# claw.net
KiCad netlist of a schematic drawn in EAGLE
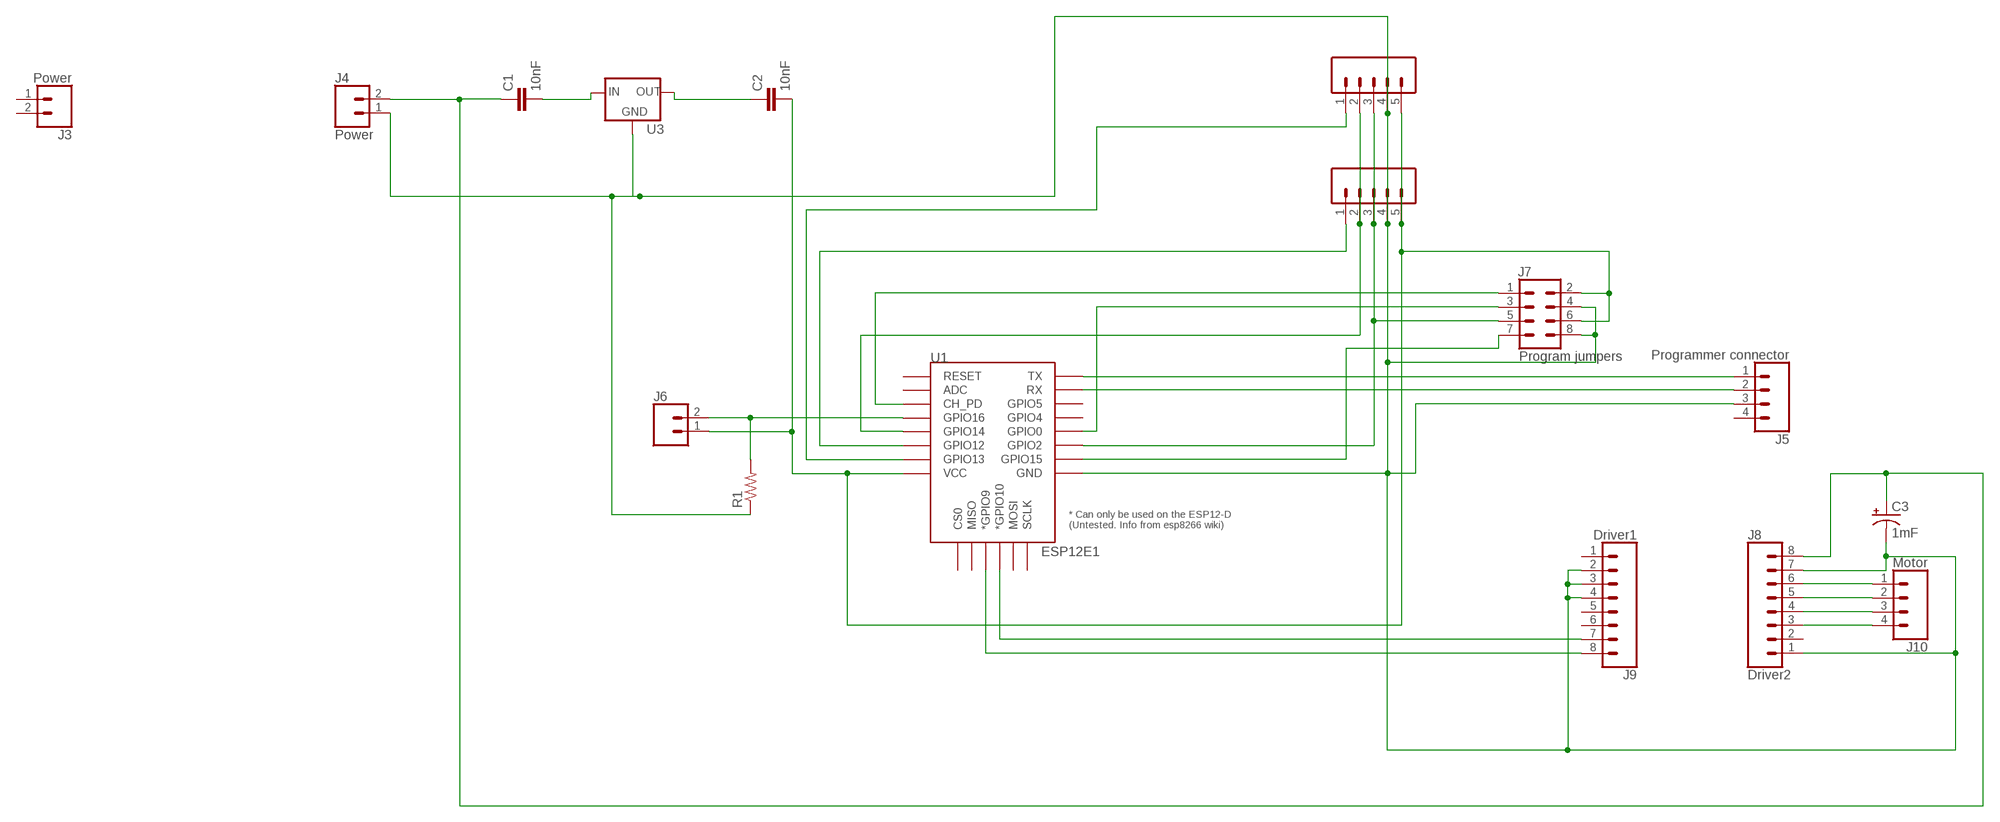
[diagram p0: schematic, sheet 1]

(export (version "E")
  (design (tool "Eeschema 10.0.6"))
  (components
    (comp (ref "C1")
      (value "10nF")
      (footprint "eagle-import:0603")
      (libsource (lib "eagle-import") (part "10NF-0603-50V-10%"))
    )
    (comp (ref "C2")
      (value "10nF")
      (footprint "eagle-import:0603")
      (libsource (lib "eagle-import") (part "10NF-0603-50V-10%"))
    )
    (comp (ref "C3")
      (value "1mF")
      (footprint "eagle-import:CPOL-RADIAL-5MM-10MM")
      (libsource (lib "eagle-import") (part "1000UF-RADIAL-5MM-25V-20%"))
    )
    (comp (ref "J1")
      (value "Sensor1")
      (footprint "eagle-import:JST-5-PTH-VERT")
      (libsource (lib "eagle-import") (part "CONN_05JST-VERT"))
    )
    (comp (ref "J2")
      (value "Sensor2")
      (footprint "eagle-import:JST-5-PTH-VERT")
      (libsource (lib "eagle-import") (part "CONN_05JST-VERT"))
    )
    (comp (ref "J3")
      (value "Power")
      (footprint "eagle-import:1X02_LOCK")
      (libsource (lib "eagle-import") (part "CONN_02LOCK"))
    )
    (comp (ref "J4")
      (value "Power")
      (footprint "eagle-import:1X02_LOCK")
      (libsource (lib "eagle-import") (part "CONN_02LOCK"))
    )
    (comp (ref "J5")
      (value "Programmer connector")
      (footprint "eagle-import:JST-4-PTH-VERT")
      (libsource (lib "eagle-import") (part "CONN_04JST-PTH-VERT"))
    )
    (comp (ref "J6")
      (value "CONN_02LOCK")
      (footprint "eagle-import:1X02_LOCK")
      (libsource (lib "eagle-import") (part "CONN_02LOCK"))
    )
    (comp (ref "J7")
      (value "Program jumpers")
      (footprint "eagle-import:2X4")
      (libsource (lib "eagle-import") (part "CONN_04X2"))
    )
    (comp (ref "J8")
      (value "Driver2")
      (footprint "eagle-import:1X08_NO_SILK")
      (libsource (lib "eagle-import") (part "CONN_08NO_SILK_FEMALE_PTH"))
    )
    (comp (ref "J9")
      (value "Driver1")
      (footprint "eagle-import:1X08_NO_SILK")
      (libsource (lib "eagle-import") (part "CONN_08NO_SILK_FEMALE_PTH"))
    )
    (comp (ref "J10")
      (value "Motor")
      (footprint "eagle-import:JST-4-PTH-VERT")
      (libsource (lib "eagle-import") (part "CONN_04JST-PTH-VERT"))
    )
    (comp (ref "R1")
      (value "R-US_M2309")
      (footprint "eagle-import:M2309")
      (libsource (lib "eagle-import") (part "R-US_M2309"))
    )
    (comp (ref "U1")
      (value "ESP12E1")
      (footprint "eagle-import:ESP12E-SMD")
      (libsource (lib "eagle-import") (part "ESP12ESMD"))
    )
    (comp (ref "U3")
      (value "V_REG_78XX-TO-220")
      (footprint "eagle-import:TO-220-ALT")
      (libsource (lib "eagle-import") (part "V_REG_78XX-TO-220"))
    )
  )
  (nets
    (net (code "1") (name "Net-(C1-Pad1)") (class "Default")
      (node (ref "C1") (pin "1") (pinfunction "1_1") (pintype "passive"))
      (node (ref "C3") (pin "+") (pinfunction "+_+") (pintype "passive"))
      (node (ref "J4") (pin "2") (pinfunction "2_2") (pintype "passive"))
      (node (ref "J8") (pin "8") (pinfunction "8_8") (pintype "passive"))
    )
    (net (code "2") (name "Net-(C1-Pad2)") (class "Default")
      (node (ref "C1") (pin "2") (pinfunction "2_2") (pintype "passive"))
      (node (ref "U3") (pin "IN") (pinfunction "IN_IN") (pintype "input"))
    )
    (net (code "3") (name "Net-(C2-Pad1)") (class "Default")
      (node (ref "C2") (pin "1") (pinfunction "1_1") (pintype "passive"))
      (node (ref "U3") (pin "OUT") (pinfunction "OUT_OUT") (pintype "passive"))
    )
    (net (code "4") (name "Net-(C2-Pad2)") (class "Default")
      (node (ref "C2") (pin "2") (pinfunction "2_2") (pintype "passive"))
      (node (ref "J1") (pin "5") (pinfunction "5_5") (pintype "passive"))
      (node (ref "J2") (pin "5") (pinfunction "5_5") (pintype "passive"))
      (node (ref "J6") (pin "1") (pinfunction "1_1") (pintype "passive"))
      (node (ref "J7") (pin "2") (pinfunction "2_2") (pintype "passive"))
      (node (ref "J7") (pin "6") (pinfunction "6_6") (pintype "passive"))
      (node (ref "U1") (pin "VCC") (pinfunction "VCC_VCC") (pintype "bidirectional"))
    )
    (net (code "5") (name "Net-(C3-Pad-)") (class "Default")
      (node (ref "C3") (pin "-") (pinfunction "-_-") (pintype "passive"))
      (node (ref "J1") (pin "4") (pinfunction "4_4") (pintype "passive"))
      (node (ref "J2") (pin "4") (pinfunction "4_4") (pintype "passive"))
      (node (ref "J4") (pin "1") (pinfunction "1_1") (pintype "passive"))
      (node (ref "J5") (pin "3") (pinfunction "3_3") (pintype "passive"))
      (node (ref "J7") (pin "4") (pinfunction "4_4") (pintype "passive"))
      (node (ref "J7") (pin "8") (pinfunction "8_8") (pintype "passive"))
      (node (ref "J8") (pin "1") (pinfunction "1_1") (pintype "passive"))
      (node (ref "J8") (pin "7") (pinfunction "7_7") (pintype "passive"))
      (node (ref "J9") (pin "2") (pinfunction "2_2") (pintype "passive"))
      (node (ref "J9") (pin "3") (pinfunction "3_3") (pintype "passive"))
      (node (ref "J9") (pin "4") (pinfunction "4_4") (pintype "passive"))
      (node (ref "R1") (pin "1") (pinfunction "1_1") (pintype "passive"))
      (node (ref "U1") (pin "GND") (pinfunction "GND_GND") (pintype "bidirectional"))
      (node (ref "U3") (pin "GND") (pinfunction "GND_GND") (pintype "input"))
    )
    (net (code "6") (name "Net-(J1-Pad1)") (class "Default")
      (node (ref "J1") (pin "1") (pinfunction "1_1") (pintype "passive"))
      (node (ref "U1") (pin "GPIO13") (pinfunction "GPIO13_GPIO13") (pintype "bidirectional"))
    )
    (net (code "7") (name "Net-(J1-Pad2)") (class "Default")
      (node (ref "J1") (pin "2") (pinfunction "2_2") (pintype "passive"))
      (node (ref "J2") (pin "2") (pinfunction "2_2") (pintype "passive"))
      (node (ref "U1") (pin "GPIO14") (pinfunction "GPIO14_GPIO14") (pintype "bidirectional"))
    )
    (net (code "8") (name "Net-(J1-Pad3)") (class "Default")
      (node (ref "J1") (pin "3") (pinfunction "3_3") (pintype "passive"))
      (node (ref "J2") (pin "3") (pinfunction "3_3") (pintype "passive"))
      (node (ref "J7") (pin "5") (pinfunction "5_5") (pintype "passive"))
      (node (ref "U1") (pin "GPIO2") (pinfunction "GPIO2_GPIO2") (pintype "bidirectional"))
    )
    (net (code "9") (name "Net-(J2-Pad1)") (class "Default")
      (node (ref "J2") (pin "1") (pinfunction "1_1") (pintype "passive"))
      (node (ref "U1") (pin "GPIO12") (pinfunction "GPIO12_GPIO12") (pintype "bidirectional"))
    )
    (net (code "10") (name "Net-(J6-Pad2)") (class "Default")
      (node (ref "J6") (pin "2") (pinfunction "2_2") (pintype "passive"))
      (node (ref "R1") (pin "2") (pinfunction "2_2") (pintype "passive"))
      (node (ref "U1") (pin "GPIO16") (pinfunction "GPIO16_GPIO16") (pintype "bidirectional"))
    )
    (net (code "11") (name "Net-(J7-Pad1)") (class "Default")
      (node (ref "J7") (pin "1") (pinfunction "1_1") (pintype "passive"))
      (node (ref "U1") (pin "CH_PD") (pinfunction "CH_PD_CH_PD") (pintype "bidirectional"))
    )
    (net (code "12") (name "Net-(J7-Pad3)") (class "Default")
      (node (ref "J7") (pin "3") (pinfunction "3_3") (pintype "passive"))
      (node (ref "U1") (pin "GPIO0") (pinfunction "GPIO0_GPIO0") (pintype "bidirectional"))
    )
    (net (code "13") (name "Net-(J7-Pad7)") (class "Default")
      (node (ref "J7") (pin "7") (pinfunction "7_7") (pintype "passive"))
      (node (ref "U1") (pin "GPIO15") (pinfunction "GPIO15_GPIO15") (pintype "bidirectional"))
    )
    (net (code "14") (name "Net-(J10-Pad1)") (class "Default")
      (node (ref "J10") (pin "1") (pinfunction "1_1") (pintype "passive"))
      (node (ref "J8") (pin "6") (pinfunction "6_6") (pintype "passive"))
    )
    (net (code "15") (name "Net-(J10-Pad2)") (class "Default")
      (node (ref "J10") (pin "2") (pinfunction "2_2") (pintype "passive"))
      (node (ref "J8") (pin "5") (pinfunction "5_5") (pintype "passive"))
    )
    (net (code "16") (name "Net-(J10-Pad3)") (class "Default")
      (node (ref "J10") (pin "3") (pinfunction "3_3") (pintype "passive"))
      (node (ref "J8") (pin "4") (pinfunction "4_4") (pintype "passive"))
    )
    (net (code "17") (name "Net-(J10-Pad4)") (class "Default")
      (node (ref "J10") (pin "4") (pinfunction "4_4") (pintype "passive"))
      (node (ref "J8") (pin "3") (pinfunction "3_3") (pintype "passive"))
    )
    (net (code "18") (name "Net-(U1-*GPIO9)") (class "Default")
      (node (ref "J9") (pin "8") (pinfunction "8_8") (pintype "passive"))
      (node (ref "U1") (pin "GPIO9") (pinfunction "*GPIO9_GPIO9") (pintype "bidirectional"))
    )
    (net (code "19") (name "Net-(U1-*GPIO10)") (class "Default")
      (node (ref "J9") (pin "7") (pinfunction "7_7") (pintype "passive"))
      (node (ref "U1") (pin "GPIO10") (pinfunction "*GPIO10_GPIO10") (pintype "bidirectional"))
    )
    (net (code "20") (name "Net-(U1-RX)") (class "Default")
      (node (ref "J5") (pin "2") (pinfunction "2_2") (pintype "passive"))
      (node (ref "U1") (pin "RXD0") (pinfunction "RX_RXD0") (pintype "bidirectional"))
    )
    (net (code "21") (name "Net-(U1-TX)") (class "Default")
      (node (ref "J5") (pin "1") (pinfunction "1_1") (pintype "passive"))
      (node (ref "U1") (pin "TXD0") (pinfunction "TX_TXD0") (pintype "bidirectional"))
    )
    (net (code "22") (name "unconnected-(J3-Pad1)") (class "Default")
      (node (ref "J3") (pin "1") (pinfunction "1_1") (pintype "passive"))
    )
    (net (code "23") (name "unconnected-(J3-Pad2)") (class "Default")
      (node (ref "J3") (pin "2") (pinfunction "2_2") (pintype "passive"))
    )
    (net (code "24") (name "unconnected-(J5-Pad4)") (class "Default")
      (node (ref "J5") (pin "4") (pinfunction "4_4") (pintype "passive"))
    )
    (net (code "25") (name "unconnected-(J8-Pad2)") (class "Default")
      (node (ref "J8") (pin "2") (pinfunction "2_2") (pintype "passive"))
    )
    (net (code "26") (name "unconnected-(J9-Pad1)") (class "Default")
      (node (ref "J9") (pin "1") (pinfunction "1_1") (pintype "passive"))
    )
    (net (code "27") (name "unconnected-(J9-Pad5)") (class "Default")
      (node (ref "J9") (pin "5") (pinfunction "5_5") (pintype "passive"))
    )
    (net (code "28") (name "unconnected-(J9-Pad6)") (class "Default")
      (node (ref "J9") (pin "6") (pinfunction "6_6") (pintype "passive"))
    )
    (net (code "29") (name "unconnected-(U1-PadADC)") (class "Default")
      (node (ref "U1") (pin "ADC") (pinfunction "ADC_ADC") (pintype "bidirectional"))
    )
    (net (code "30") (name "unconnected-(U1-PadCS0)") (class "Default")
      (node (ref "U1") (pin "CS0") (pinfunction "CS0_CS0") (pintype "bidirectional"))
    )
    (net (code "31") (name "unconnected-(U1-PadGPIO4)") (class "Default")
      (node (ref "U1") (pin "GPIO4") (pinfunction "GPIO4_GPIO4") (pintype "bidirectional"))
    )
    (net (code "32") (name "unconnected-(U1-PadGPIO5)") (class "Default")
      (node (ref "U1") (pin "GPIO5") (pinfunction "GPIO5_GPIO5") (pintype "bidirectional"))
    )
    (net (code "33") (name "unconnected-(U1-PadMISO)") (class "Default")
      (node (ref "U1") (pin "MISO") (pinfunction "MISO_MISO") (pintype "bidirectional"))
    )
    (net (code "34") (name "unconnected-(U1-PadMOSI)") (class "Default")
      (node (ref "U1") (pin "MOSI") (pinfunction "MOSI_MOSI") (pintype "bidirectional"))
    )
    (net (code "35") (name "unconnected-(U1-PadRESET)") (class "Default")
      (node (ref "U1") (pin "RESET") (pinfunction "RESET_RESET") (pintype "bidirectional"))
    )
    (net (code "36") (name "unconnected-(U1-PadSCLK)") (class "Default")
      (node (ref "U1") (pin "SCLK") (pinfunction "SCLK_SCLK") (pintype "bidirectional"))
    )
  )
)
